# Quadcopter_Motor_Driver_Schematic.net
KiCad netlist of a schematic drawn in EAGLE
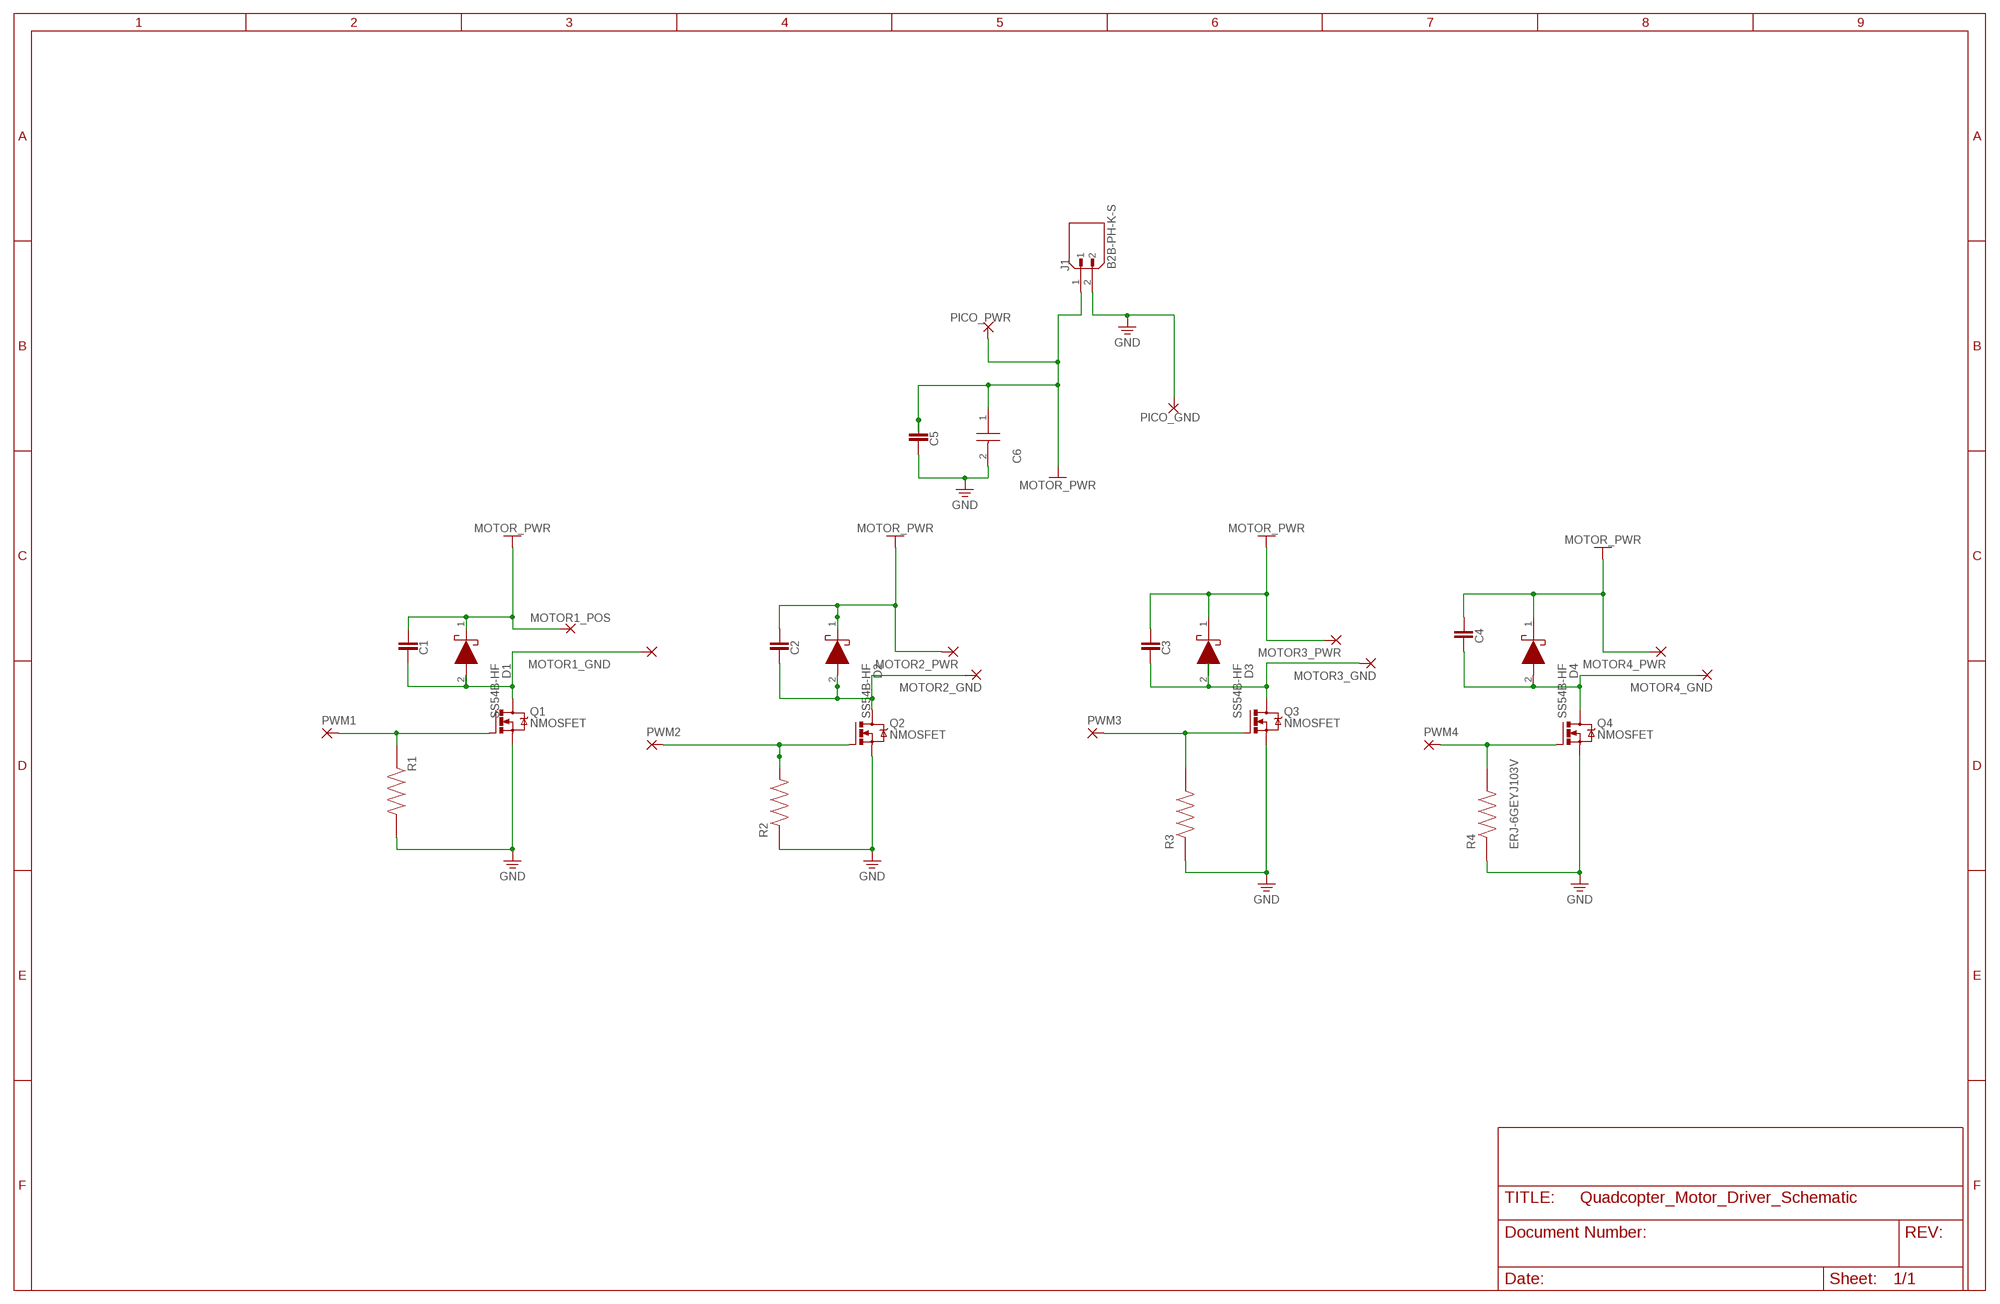
[diagram p0: schematic, sheet 1]

(export (version "E")
  (design (tool "Eeschema 10.0.6"))
  (components
    (comp (ref "C1")
      (value "CAPACITOR_CHIP-0402(1005-METRIC)")
      (footprint "eagle-import:CAPC1005X60")
      (libsource (lib "eagle-import") (part "CAPACITORCHIP-0402(1005-METRIC)_"))
    )
    (comp (ref "C2")
      (value "CAPACITOR_CHIP-0402(1005-METRIC)")
      (footprint "eagle-import:CAPC1005X60")
      (libsource (lib "eagle-import") (part "CAPACITORCHIP-0402(1005-METRIC)_"))
    )
    (comp (ref "C3")
      (value "CAPACITOR_CHIP-0402(1005-METRIC)")
      (footprint "eagle-import:CAPC1005X60")
      (libsource (lib "eagle-import") (part "CAPACITORCHIP-0402(1005-METRIC)_"))
    )
    (comp (ref "C4")
      (value "CAPACITOR_CHIP-0402(1005-METRIC)")
      (footprint "eagle-import:CAPC1005X60")
      (libsource (lib "eagle-import") (part "CAPACITORCHIP-0402(1005-METRIC)_"))
    )
    (comp (ref "C5")
      (value "CAPACITOR_CHIP-0402(1005-METRIC)")
      (footprint "eagle-import:CAPC1005X60")
      (libsource (lib "eagle-import") (part "CAPACITORCHIP-0402(1005-METRIC)_"))
    )
    (comp (ref "C6")
      (value "REA010M2CBK-0511P")
      (footprint "eagle-import:CAPPRD200W50D525H1250")
      (fields (field (name "MOUSER_PART_NUMBER") "140-REA1R0M2CBK0511P"))
      (libsource (lib "eagle-import") (part "REA010M2CBK-0511P"))
    )
    (comp (ref "D1")
      (value "SS54B-HF")
      (footprint "eagle-import:DIOM5235X244N")
      (fields (field (name "MOUSER_PART_NUMBER") "750-SS54B-HF"))
      (libsource (lib "eagle-import") (part "SS54B-HF"))
    )
    (comp (ref "D2")
      (value "SS54B-HF")
      (footprint "eagle-import:DIOM5235X244N")
      (fields (field (name "MOUSER_PART_NUMBER") "750-SS54B-HF"))
      (libsource (lib "eagle-import") (part "SS54B-HF"))
    )
    (comp (ref "D3")
      (value "SS54B-HF")
      (footprint "eagle-import:DIOM5235X244N")
      (fields (field (name "MOUSER_PART_NUMBER") "750-SS54B-HF"))
      (libsource (lib "eagle-import") (part "SS54B-HF"))
    )
    (comp (ref "D4")
      (value "SS54B-HF")
      (footprint "eagle-import:DIOM5235X244N")
      (fields (field (name "MOUSER_PART_NUMBER") "750-SS54B-HF"))
      (libsource (lib "eagle-import") (part "SS54B-HF"))
    )
    (comp (ref "J1")
      (value "B2B-PH-K-S")
      (footprint "eagle-import:JST_B2B-PH-K-S")
      (fields (field (name "MANUFACTURER") "JST"))
      (libsource (lib "eagle-import") (part "B2B-PH-K-S"))
    )
    (comp (ref "MOTOR1_GND")
      (value "1,6/0,8")
      (footprint "eagle-import:1,6_0,8")
      (libsource (lib "eagle-import") (part "1,6/0,8"))
    )
    (comp (ref "MOTOR1_POS")
      (value "1,6/0,8")
      (footprint "eagle-import:1,6_0,8")
      (libsource (lib "eagle-import") (part "1,6/0,8"))
    )
    (comp (ref "MOTOR2_GND")
      (value "1,6/0,8")
      (footprint "eagle-import:1,6_0,8")
      (libsource (lib "eagle-import") (part "1,6/0,8"))
    )
    (comp (ref "MOTOR2_PWR")
      (value "1,6/0,8")
      (footprint "eagle-import:1,6_0,8")
      (libsource (lib "eagle-import") (part "1,6/0,8"))
    )
    (comp (ref "MOTOR3_GND")
      (value "1,6/0,8")
      (footprint "eagle-import:1,6_0,8")
      (libsource (lib "eagle-import") (part "1,6/0,8"))
    )
    (comp (ref "MOTOR3_PWR")
      (value "1,6/0,8")
      (footprint "eagle-import:1,6_0,8")
      (libsource (lib "eagle-import") (part "1,6/0,8"))
    )
    (comp (ref "MOTOR4_GND")
      (value "1,6/0,8")
      (footprint "eagle-import:1,6_0,8")
      (libsource (lib "eagle-import") (part "1,6/0,8"))
    )
    (comp (ref "MOTOR4_PWR")
      (value "1,6/0,8")
      (footprint "eagle-import:1,6_0,8")
      (libsource (lib "eagle-import") (part "1,6/0,8"))
    )
    (comp (ref "PICO_GND")
      (value "1,6/0,8")
      (footprint "eagle-import:1,6_0,8")
      (libsource (lib "eagle-import") (part "1,6/0,8"))
    )
    (comp (ref "PICO_PWR")
      (value "1,6/0,8")
      (footprint "eagle-import:1,6_0,8")
      (libsource (lib "eagle-import") (part "1,6/0,8"))
    )
    (comp (ref "PWM1")
      (value "1,6/0,8")
      (footprint "eagle-import:1,6_0,8")
      (libsource (lib "eagle-import") (part "1,6/0,8"))
    )
    (comp (ref "PWM2")
      (value "1,6/0,8")
      (footprint "eagle-import:1,6_0,8")
      (libsource (lib "eagle-import") (part "1,6/0,8"))
    )
    (comp (ref "PWM3")
      (value "1,6/0,8")
      (footprint "eagle-import:1,6_0,8")
      (libsource (lib "eagle-import") (part "1,6/0,8"))
    )
    (comp (ref "PWM4")
      (value "1,6/0,8")
      (footprint "eagle-import:1,6_0,8")
      (libsource (lib "eagle-import") (part "1,6/0,8"))
    )
    (comp (ref "Q1")
      (value "NMOSFET")
      (footprint "eagle-import:SOT23")
      (libsource (lib "eagle-import") (part "NMOSFET_SOT23"))
    )
    (comp (ref "Q2")
      (value "NMOSFET")
      (footprint "eagle-import:SOT23")
      (libsource (lib "eagle-import") (part "NMOSFETSOT23-GSD"))
    )
    (comp (ref "Q3")
      (value "NMOSFET")
      (footprint "eagle-import:SOT23")
      (libsource (lib "eagle-import") (part "NMOSFETSOT23-GSD"))
    )
    (comp (ref "Q4")
      (value "NMOSFET")
      (footprint "eagle-import:SOT23")
      (libsource (lib "eagle-import") (part "NMOSFETSOT23-GSD"))
    )
    (comp (ref "R1")
      (value "ERJ-6GEYJ103V")
      (footprint "eagle-import:RES_ERJ-6GEYJ103V")
      (fields (field (name "MANUFACTURER") "Panasonic"))
      (libsource (lib "eagle-import") (part "ERJ-6GEYJ103V"))
    )
    (comp (ref "R2")
      (value "ERJ-6GEYJ103V")
      (footprint "eagle-import:RES_ERJ-6GEYJ103V")
      (fields (field (name "MANUFACTURER") "Panasonic"))
      (libsource (lib "eagle-import") (part "ERJ-6GEYJ103V"))
    )
    (comp (ref "R3")
      (value "ERJ-6GEYJ103V")
      (footprint "eagle-import:RES_ERJ-6GEYJ103V")
      (fields (field (name "MANUFACTURER") "Panasonic"))
      (libsource (lib "eagle-import") (part "ERJ-6GEYJ103V"))
    )
    (comp (ref "R4")
      (value "ERJ-6GEYJ103V")
      (footprint "eagle-import:RES_ERJ-6GEYJ103V")
      (fields (field (name "MANUFACTURER") "Panasonic"))
      (libsource (lib "eagle-import") (part "ERJ-6GEYJ103V"))
    )
  )
  (nets
    (net (code "1") (name "GND") (class "Default")
      (node (ref "C5") (pin "1") (pinfunction "1_1") (pintype "passive"))
      (node (ref "C6") (pin "2") (pinfunction "-_2") (pintype "bidirectional"))
      (node (ref "J1") (pin "2") (pinfunction "2_2") (pintype "passive"))
      (node (ref "PICO_GND") (pin "1") (pinfunction "P_1") (pintype "passive"))
      (node (ref "Q1") (pin "2") (pinfunction "S_2") (pintype "passive"))
      (node (ref "Q2") (pin "2") (pinfunction "S_2") (pintype "passive"))
      (node (ref "Q3") (pin "2") (pinfunction "S_2") (pintype "passive"))
      (node (ref "Q4") (pin "2") (pinfunction "S_2") (pintype "passive"))
      (node (ref "R1") (pin "2") (pinfunction "2_2") (pintype "passive"))
      (node (ref "R2") (pin "1") (pinfunction "1_1") (pintype "passive"))
      (node (ref "R3") (pin "1") (pinfunction "1_1") (pintype "passive"))
      (node (ref "R4") (pin "1") (pinfunction "1_1") (pintype "passive"))
    )
    (net (code "2") (name "MOTOR_PWR") (class "Default")
      (node (ref "C1") (pin "2") (pinfunction "2_2") (pintype "passive"))
      (node (ref "C2") (pin "2") (pinfunction "2_2") (pintype "passive"))
      (node (ref "C3") (pin "2") (pinfunction "2_2") (pintype "passive"))
      (node (ref "C4") (pin "2") (pinfunction "2_2") (pintype "passive"))
      (node (ref "C5") (pin "2") (pinfunction "2_2") (pintype "passive"))
      (node (ref "C6") (pin "1") (pinfunction "+_1") (pintype "bidirectional"))
      (node (ref "D1") (pin "1") (pinfunction "K_1") (pintype "bidirectional"))
      (node (ref "D2") (pin "1") (pinfunction "K_1") (pintype "bidirectional"))
      (node (ref "D3") (pin "1") (pinfunction "K_1") (pintype "bidirectional"))
      (node (ref "D4") (pin "1") (pinfunction "K_1") (pintype "bidirectional"))
      (node (ref "J1") (pin "1") (pinfunction "1_1") (pintype "passive"))
      (node (ref "MOTOR1_POS") (pin "1") (pinfunction "P_1") (pintype "passive"))
      (node (ref "MOTOR2_PWR") (pin "1") (pinfunction "P_1") (pintype "passive"))
      (node (ref "MOTOR3_PWR") (pin "1") (pinfunction "P_1") (pintype "passive"))
      (node (ref "MOTOR4_PWR") (pin "1") (pinfunction "P_1") (pintype "passive"))
      (node (ref "PICO_PWR") (pin "1") (pinfunction "P_1") (pintype "passive"))
    )
    (net (code "3") (name "Net-(D1-A)") (class "Default")
      (node (ref "C1") (pin "1") (pinfunction "1_1") (pintype "passive"))
      (node (ref "D1") (pin "2") (pinfunction "A_2") (pintype "bidirectional"))
      (node (ref "MOTOR1_GND") (pin "1") (pinfunction "P_1") (pintype "passive"))
      (node (ref "Q1") (pin "3") (pinfunction "D_3") (pintype "passive"))
    )
    (net (code "4") (name "Net-(D2-A)") (class "Default")
      (node (ref "C2") (pin "1") (pinfunction "1_1") (pintype "passive"))
      (node (ref "D2") (pin "2") (pinfunction "A_2") (pintype "bidirectional"))
      (node (ref "MOTOR2_GND") (pin "1") (pinfunction "P_1") (pintype "passive"))
      (node (ref "Q2") (pin "3") (pinfunction "D_3") (pintype "passive"))
    )
    (net (code "5") (name "Net-(D3-A)") (class "Default")
      (node (ref "C3") (pin "1") (pinfunction "1_1") (pintype "passive"))
      (node (ref "D3") (pin "2") (pinfunction "A_2") (pintype "bidirectional"))
      (node (ref "MOTOR3_GND") (pin "1") (pinfunction "P_1") (pintype "passive"))
      (node (ref "Q3") (pin "3") (pinfunction "D_3") (pintype "passive"))
    )
    (net (code "6") (name "Net-(D4-A)") (class "Default")
      (node (ref "C4") (pin "1") (pinfunction "1_1") (pintype "passive"))
      (node (ref "D4") (pin "2") (pinfunction "A_2") (pintype "bidirectional"))
      (node (ref "MOTOR4_GND") (pin "1") (pinfunction "P_1") (pintype "passive"))
      (node (ref "Q4") (pin "3") (pinfunction "D_3") (pintype "passive"))
    )
    (net (code "7") (name "Net-(PWM1-P)") (class "Default")
      (node (ref "PWM1") (pin "1") (pinfunction "P_1") (pintype "passive"))
      (node (ref "Q1") (pin "1") (pinfunction "G_1") (pintype "passive"))
      (node (ref "R1") (pin "1") (pinfunction "1_1") (pintype "passive"))
    )
    (net (code "8") (name "Net-(PWM2-P)") (class "Default")
      (node (ref "PWM2") (pin "1") (pinfunction "P_1") (pintype "passive"))
      (node (ref "Q2") (pin "1") (pinfunction "G_1") (pintype "passive"))
      (node (ref "R2") (pin "2") (pinfunction "2_2") (pintype "passive"))
    )
    (net (code "9") (name "Net-(PWM3-P)") (class "Default")
      (node (ref "PWM3") (pin "1") (pinfunction "P_1") (pintype "passive"))
      (node (ref "Q3") (pin "1") (pinfunction "G_1") (pintype "passive"))
      (node (ref "R3") (pin "2") (pinfunction "2_2") (pintype "passive"))
    )
    (net (code "10") (name "Net-(PWM4-P)") (class "Default")
      (node (ref "PWM4") (pin "1") (pinfunction "P_1") (pintype "passive"))
      (node (ref "Q4") (pin "1") (pinfunction "G_1") (pintype "passive"))
      (node (ref "R4") (pin "2") (pinfunction "2_2") (pintype "passive"))
    )
  )
)
